# Poly_Piezo.net
KiCad netlist of a schematic drawn in EAGLE
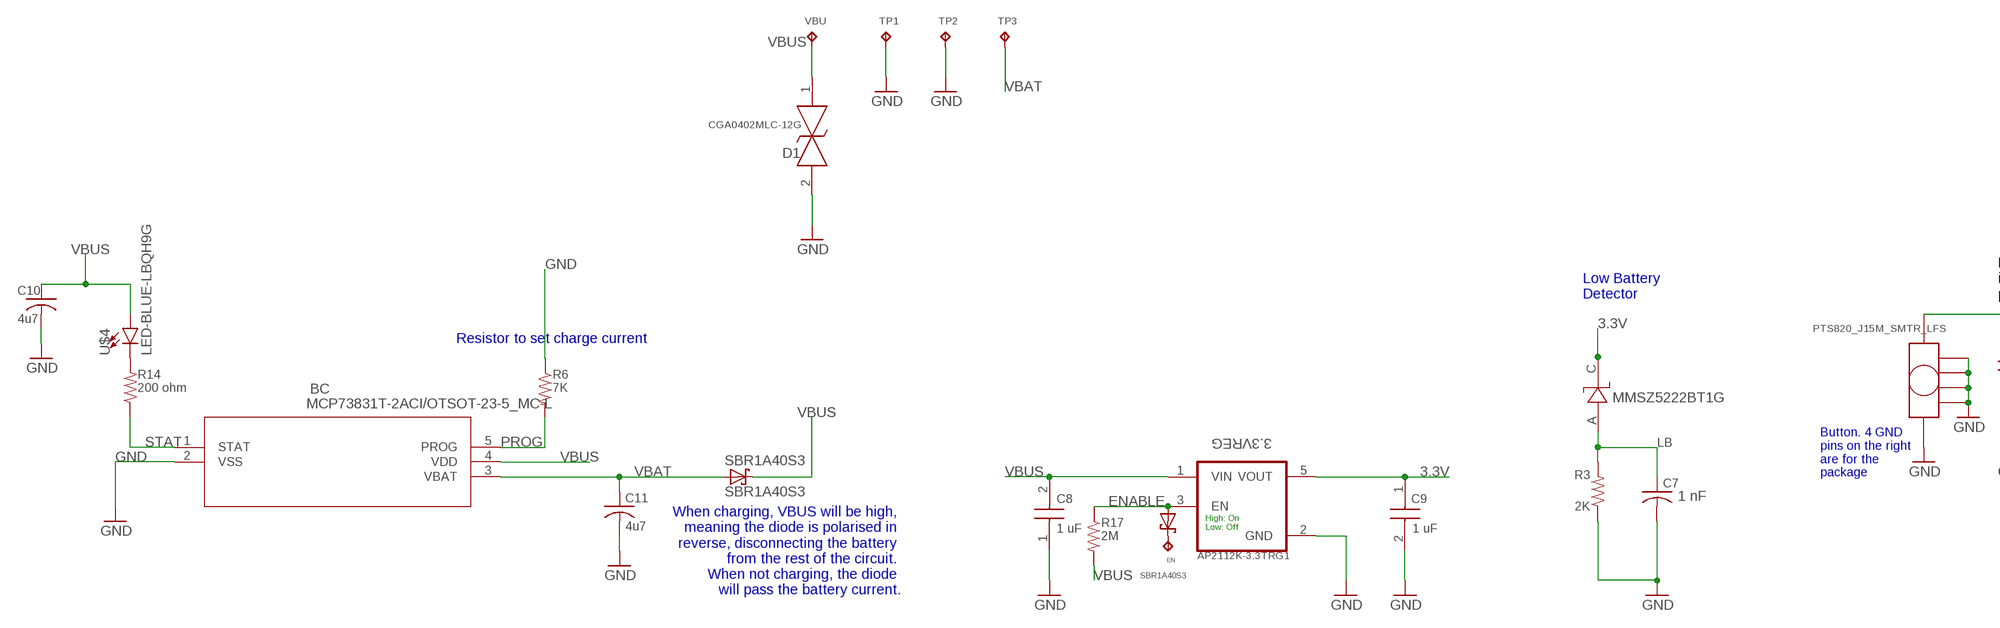
[diagram p0: schematic, sheet 1, part 1 of 2]
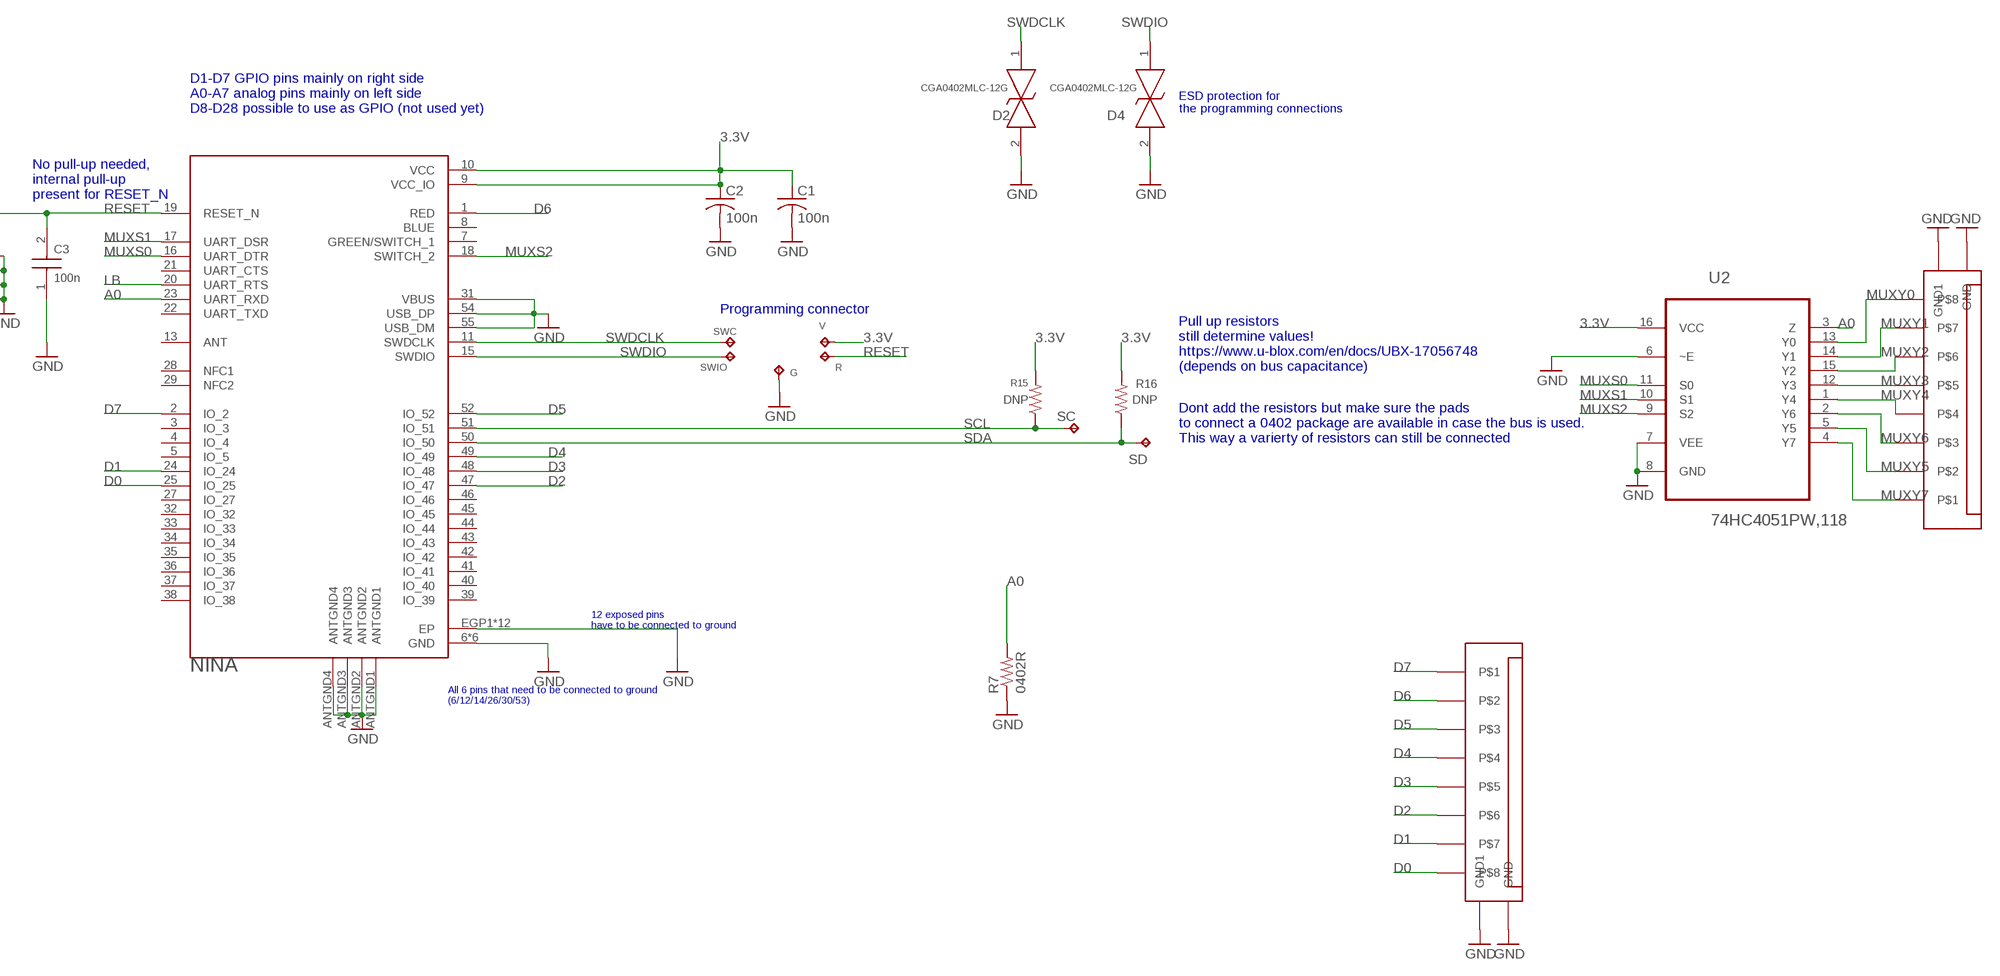
[diagram p1: schematic, sheet 1, part 2 of 2]

(export (version "E")
  (design (tool "Eeschema 10.0.6"))
  (components
    (comp (ref "3.3VREG")
      (value "AP2112K-3.3TRG1")
      (footprint "eagle-import:SOT95P285X140-5N")
      (fields (field (name "MF") "Diodes Inc."))
      (libsource (lib "eagle-import") (part "AP2112K-3.3TRG1"))
    )
    (comp (ref "BC")
      (value "MCP73831T-2ACI/OTSOT-23-5_MC-L")
      (footprint "eagle-import:SOT-23-5_MC-L")
      (fields (field (name "MANUFACTURER_PART_NUMBER") "MCP73831T-2ACI/OT"))
      (libsource (lib "eagle-import") (part "MCP73831T-2ACI/OTSOT-23-5_MC-L"))
    )
    (comp (ref "BUTTON")
      (value "PTS820_J15M_SMTR_LFS")
      (footprint "eagle-import:PTS820_J15")
      (fields
        (field (name "MANUFACTURER_PART_NUMBER") "PTS820 J15M SMTR LFS")
        (field (name "MOUSER_PART_NUMBER") "611-PTS820J15MSMTR")
        (field (name "RS_PART_NUMBER") "1359503P")
      )
      (libsource (lib "eagle-import") (part "PTS820_J15M_SMTR_LFS"))
    )
    (comp (ref "C1")
      (value "100n")
      (footprint "eagle-import:C0402")
      (libsource (lib "eagle-import") (part "C-USC0402"))
    )
    (comp (ref "C2")
      (value "100n")
      (footprint "eagle-import:C0402")
      (libsource (lib "eagle-import") (part "C-USC0402"))
    )
    (comp (ref "C3")
      (value "100n")
      (footprint "eagle-import:CAPC1005X33N")
      (fields
        (field (name "MANUFACTURER_PART_NUMBER") "JMK105BJ105KP-F")
        (field (name "MOUSER_PART_NUMBER") "963-JMK105BJ105KP-F")
      )
      (libsource (lib "eagle-import") (part "JMK105BJ105KP-F"))
    )
    (comp (ref "C7")
      (value "1 nF")
      (footprint "eagle-import:C0402")
      (libsource (lib "eagle-import") (part "C-USC0402"))
    )
    (comp (ref "C8")
      (value "1 uF")
      (footprint "eagle-import:CAPC1005X33N")
      (fields
        (field (name "MANUFACTURER_PART_NUMBER") "JMK105BJ105KP-F")
        (field (name "MOUSER_PART_NUMBER") "963-JMK105BJ105KP-F")
      )
      (libsource (lib "eagle-import") (part "JMK105BJ105KP-F"))
    )
    (comp (ref "C9")
      (value "1 uF")
      (footprint "eagle-import:CAPC1005X33N")
      (fields
        (field (name "MANUFACTURER_PART_NUMBER") "JMK105BJ105KP-F")
        (field (name "MOUSER_PART_NUMBER") "963-JMK105BJ105KP-F")
      )
      (libsource (lib "eagle-import") (part "JMK105BJ105KP-F"))
    )
    (comp (ref "C10")
      (value "4u7")
      (footprint "eagle-import:C0402")
      (libsource (lib "eagle-import") (part "C-USC0402"))
    )
    (comp (ref "C11")
      (value "4u7")
      (footprint "eagle-import:C0402")
      (libsource (lib "eagle-import") (part "C-USC0402"))
    )
    (comp (ref "D1")
      (value "CGA0402MLC-12G")
      (footprint "eagle-import:CGA0402MLC12G")
      (fields (field (name "MOUSER_PART_NUMBER") "652-CGA0402MLC-12G"))
      (libsource (lib "eagle-import") (part "CGA0402MLC-12G"))
    )
    (comp (ref "D2")
      (value "CGA0402MLC-12G")
      (footprint "eagle-import:CGA0402MLC12G")
      (fields (field (name "MOUSER_PART_NUMBER") "652-CGA0402MLC-12G"))
      (libsource (lib "eagle-import") (part "CGA0402MLC-12G"))
    )
    (comp (ref "D4")
      (value "CGA0402MLC-12G")
      (footprint "eagle-import:CGA0402MLC12G")
      (fields (field (name "MOUSER_PART_NUMBER") "652-CGA0402MLC-12G"))
      (libsource (lib "eagle-import") (part "CGA0402MLC-12G"))
    )
    (comp (ref "EN")
      (value "CUSTOM_HOLE1")
      (footprint "eagle-import:CUSTOM_HOLE")
      (libsource (lib "eagle-import") (part "CUSTOM_HOLE1"))
    )
    (comp (ref "G")
      (value "TPB1,27")
      (footprint "eagle-import:B1,27")
      (libsource (lib "eagle-import") (part "TPB1,27"))
    )
    (comp (ref "MMSZ5222BT1G")
      (value "MMSZ5222BT1G")
      (footprint "eagle-import:SOD−123")
      (libsource (lib "eagle-import") (part "MMSZ5222BT1G"))
    )
    (comp (ref "R")
      (value "TPB1,27")
      (footprint "eagle-import:B1,27")
      (libsource (lib "eagle-import") (part "TPB1,27"))
    )
    (comp (ref "R3")
      (value "2K")
      (footprint "eagle-import:RESC1005X40N")
      (libsource (lib "eagle-import") (part "0402R"))
    )
    (comp (ref "R6")
      (value "7K")
      (footprint "eagle-import:RESC1005X40N")
      (libsource (lib "eagle-import") (part "0402R"))
    )
    (comp (ref "R7")
      (value "0402R")
      (footprint "eagle-import:RESC1005X40N")
      (libsource (lib "eagle-import") (part "0402R"))
    )
    (comp (ref "R14")
      (value "200 ohm")
      (footprint "eagle-import:RESC1005X40N")
      (libsource (lib "eagle-import") (part "0402R"))
    )
    (comp (ref "R15")
      (value "DNP")
      (footprint "eagle-import:RESC1005X40N")
      (libsource (lib "eagle-import") (part "0402R"))
    )
    (comp (ref "R16")
      (value "DNP")
      (footprint "eagle-import:RESC1005X40N")
      (libsource (lib "eagle-import") (part "0402R"))
    )
    (comp (ref "R17")
      (value "2M")
      (footprint "eagle-import:RESC1005X40N")
      (libsource (lib "eagle-import") (part "0402R"))
    )
    (comp (ref "SBR1A40S3")
      (value "SBR1A40S3")
      (footprint "eagle-import:SOD323")
      (libsource (lib "eagle-import") (part "SBR1A40S3"))
    )
    (comp (ref "SC")
      (value "CUSTOM_HOLE1")
      (footprint "eagle-import:CUSTOM_HOLE")
      (libsource (lib "eagle-import") (part "CUSTOM_HOLE1"))
    )
    (comp (ref "SD")
      (value "CUSTOM_HOLE1")
      (footprint "eagle-import:CUSTOM_HOLE")
      (libsource (lib "eagle-import") (part "CUSTOM_HOLE1"))
    )
    (comp (ref "SWC")
      (value "TPB1,27")
      (footprint "eagle-import:B1,27")
      (libsource (lib "eagle-import") (part "TPB1,27"))
    )
    (comp (ref "SWIO")
      (value "TPB1,27")
      (footprint "eagle-import:B1,27")
      (libsource (lib "eagle-import") (part "TPB1,27"))
    )
    (comp (ref "TP1")
      (value "CUSTOM_HOLE1")
      (footprint "eagle-import:CUSTOM_HOLE")
      (libsource (lib "eagle-import") (part "CUSTOM_HOLE1"))
    )
    (comp (ref "TP2")
      (value "CUSTOM_HOLE1")
      (footprint "eagle-import:CUSTOM_HOLE")
      (libsource (lib "eagle-import") (part "CUSTOM_HOLE1"))
    )
    (comp (ref "TP3")
      (value "CUSTOM_HOLE1")
      (footprint "eagle-import:CUSTOM_HOLE")
      (libsource (lib "eagle-import") (part "CUSTOM_HOLE1"))
    )
    (comp (ref "U$1")
      (value "XF3M(1)-0815-1B")
      (footprint "eagle-import:XF3M(1)-0815-1B")
      (libsource (lib "eagle-import") (part "XF3M(1)-0815-1B"))
    )
    (comp (ref "U$2")
      (value "SBR1A40S3")
      (footprint "eagle-import:SOD323")
      (libsource (lib "eagle-import") (part "SBR1A40S3"))
    )
    (comp (ref "U$3")
      (value "XF3M(1)-0815-1B")
      (footprint "eagle-import:XF3M(1)-0815-1B")
      (libsource (lib "eagle-import") (part "XF3M(1)-0815-1B"))
    )
    (comp (ref "U$4")
      (value "LED-BLUE-LBQH9G")
      (footprint "eagle-import:LBQH9G-0402")
      (libsource (lib "eagle-import") (part "LED-BLUE-LBQH9G"))
    )
    (comp (ref "U1")
      (value "NINA")
      (footprint "eagle-import:XCVR_NINA-B306")
      (fields (field (name "MF") "U-Blox America Inc.") (field (name "MP") "NINA-B311-00B"))
      (libsource (lib "eagle-import") (part "NINA-B306"))
    )
    (comp (ref "U2")
      (value "74HC4051PW,118")
      (footprint "eagle-import:SOP65P640X110-16N")
      (fields (field (name "MF") "Nexperia USA Inc."))
      (libsource (lib "eagle-import") (part "74HC4051PW,118"))
    )
    (comp (ref "V")
      (value "TPB1,27")
      (footprint "eagle-import:B1,27")
      (libsource (lib "eagle-import") (part "TPB1,27"))
    )
    (comp (ref "VBU")
      (value "CUSTOM_HOLE1")
      (footprint "eagle-import:CUSTOM_HOLE")
      (libsource (lib "eagle-import") (part "CUSTOM_HOLE1"))
    )
  )
  (nets
    (net (code "1") (name "/3.3V") (class "Default")
      (node (ref "3.3VREG") (pin "5") (pinfunction "VOUT_5") (pintype "power_in"))
      (node (ref "C1") (pin "1") (pinfunction "1_1") (pintype "passive"))
      (node (ref "C2") (pin "1") (pinfunction "1_1") (pintype "passive"))
      (node (ref "C9") (pin "1") (pinfunction "1_1") (pintype "bidirectional"))
      (node (ref "MMSZ5222BT1G") (pin "C") (pinfunction "C_C") (pintype "bidirectional"))
      (node (ref "R15") (pin "2") (pinfunction "2_2") (pintype "passive"))
      (node (ref "R16") (pin "2") (pinfunction "2_2") (pintype "passive"))
      (node (ref "U1") (pin "10") (pinfunction "VCC_10") (pintype "power_in"))
      (node (ref "U1") (pin "9") (pinfunction "VCC_IO_9") (pintype "power_in"))
      (node (ref "U2") (pin "16") (pinfunction "VCC_16") (pintype "power_in"))
      (node (ref "V") (pin "TP") (pinfunction "TP_TP") (pintype "input"))
    )
    (net (code "2") (name "/A0") (class "Default")
      (node (ref "R7") (pin "2") (pinfunction "2_2") (pintype "passive"))
      (node (ref "U1") (pin "23") (pinfunction "UART_RXD_23") (pintype "input"))
      (node (ref "U2") (pin "3") (pinfunction "Z_3") (pintype "bidirectional"))
    )
    (net (code "3") (name "/D0") (class "Default")
      (node (ref "U$1") (pin "P$8") (pinfunction "P$8_P$8") (pintype "bidirectional"))
      (node (ref "U1") (pin "25") (pinfunction "IO_25_25") (pintype "bidirectional"))
    )
    (net (code "4") (name "/D1") (class "Default")
      (node (ref "U$1") (pin "P$7") (pinfunction "P$7_P$7") (pintype "bidirectional"))
      (node (ref "U1") (pin "24") (pinfunction "IO_24_24") (pintype "bidirectional"))
    )
    (net (code "5") (name "/D2") (class "Default")
      (node (ref "U$1") (pin "P$6") (pinfunction "P$6_P$6") (pintype "bidirectional"))
      (node (ref "U1") (pin "47") (pinfunction "IO_47_47") (pintype "bidirectional"))
    )
    (net (code "6") (name "/D3") (class "Default")
      (node (ref "U$1") (pin "P$5") (pinfunction "P$5_P$5") (pintype "bidirectional"))
      (node (ref "U1") (pin "48") (pinfunction "IO_48_48") (pintype "bidirectional"))
    )
    (net (code "7") (name "/D4") (class "Default")
      (node (ref "U$1") (pin "P$4") (pinfunction "P$4_P$4") (pintype "bidirectional"))
      (node (ref "U1") (pin "49") (pinfunction "IO_49_49") (pintype "bidirectional"))
    )
    (net (code "8") (name "/D5") (class "Default")
      (node (ref "U$1") (pin "P$3") (pinfunction "P$3_P$3") (pintype "bidirectional"))
      (node (ref "U1") (pin "52") (pinfunction "IO_52_52") (pintype "bidirectional"))
    )
    (net (code "9") (name "/D6") (class "Default")
      (node (ref "U$1") (pin "P$2") (pinfunction "P$2_P$2") (pintype "bidirectional"))
      (node (ref "U1") (pin "1") (pinfunction "RED_1") (pintype "output"))
    )
    (net (code "10") (name "/D7") (class "Default")
      (node (ref "U$1") (pin "P$1") (pinfunction "P$1_P$1") (pintype "bidirectional"))
      (node (ref "U1") (pin "2") (pinfunction "IO_2_2") (pintype "bidirectional"))
    )
    (net (code "11") (name "/ENABLE") (class "Default")
      (node (ref "3.3VREG") (pin "3") (pinfunction "EN_3") (pintype "input"))
      (node (ref "R17") (pin "1") (pinfunction "1_1") (pintype "passive"))
      (node (ref "U$2") (pin "A") (pinfunction "A_A") (pintype "passive"))
    )
    (net (code "12") (name "/LB") (class "Default")
      (node (ref "C7") (pin "1") (pinfunction "1_1") (pintype "passive"))
      (node (ref "MMSZ5222BT1G") (pin "A") (pinfunction "A_A") (pintype "bidirectional"))
      (node (ref "R3") (pin "2") (pinfunction "2_2") (pintype "passive"))
      (node (ref "U1") (pin "20") (pinfunction "UART_RTS_20") (pintype "output"))
    )
    (net (code "13") (name "/MUXS0") (class "Default")
      (node (ref "U1") (pin "16") (pinfunction "UART_DTR_16") (pintype "output"))
      (node (ref "U2") (pin "11") (pinfunction "S0_11") (pintype "input"))
    )
    (net (code "14") (name "/MUXS1") (class "Default")
      (node (ref "U1") (pin "17") (pinfunction "UART_DSR_17") (pintype "input"))
      (node (ref "U2") (pin "10") (pinfunction "S1_10") (pintype "input"))
    )
    (net (code "15") (name "/MUXS2") (class "Default")
      (node (ref "U1") (pin "18") (pinfunction "SWITCH_2_18") (pintype "input"))
      (node (ref "U2") (pin "9") (pinfunction "S2_9") (pintype "input"))
    )
    (net (code "16") (name "/MUXY0") (class "Default")
      (node (ref "U$3") (pin "P$8") (pinfunction "P$8_P$8") (pintype "bidirectional"))
      (node (ref "U2") (pin "13") (pinfunction "Y0_13") (pintype "bidirectional"))
    )
    (net (code "17") (name "/MUXY1") (class "Default")
      (node (ref "U$3") (pin "P$7") (pinfunction "P$7_P$7") (pintype "bidirectional"))
      (node (ref "U2") (pin "14") (pinfunction "Y1_14") (pintype "bidirectional"))
    )
    (net (code "18") (name "/MUXY2") (class "Default")
      (node (ref "U$3") (pin "P$6") (pinfunction "P$6_P$6") (pintype "bidirectional"))
      (node (ref "U2") (pin "15") (pinfunction "Y2_15") (pintype "bidirectional"))
    )
    (net (code "19") (name "/MUXY3") (class "Default")
      (node (ref "U$3") (pin "P$5") (pinfunction "P$5_P$5") (pintype "bidirectional"))
      (node (ref "U2") (pin "12") (pinfunction "Y3_12") (pintype "bidirectional"))
    )
    (net (code "20") (name "/MUXY4") (class "Default")
      (node (ref "U$3") (pin "P$4") (pinfunction "P$4_P$4") (pintype "bidirectional"))
      (node (ref "U2") (pin "1") (pinfunction "Y4_1") (pintype "bidirectional"))
    )
    (net (code "21") (name "/MUXY5") (class "Default")
      (node (ref "U$3") (pin "P$2") (pinfunction "P$2_P$2") (pintype "bidirectional"))
      (node (ref "U2") (pin "5") (pinfunction "Y5_5") (pintype "bidirectional"))
    )
    (net (code "22") (name "/MUXY6") (class "Default")
      (node (ref "U$3") (pin "P$3") (pinfunction "P$3_P$3") (pintype "bidirectional"))
      (node (ref "U2") (pin "2") (pinfunction "Y6_2") (pintype "bidirectional"))
    )
    (net (code "23") (name "/MUXY7") (class "Default")
      (node (ref "U$3") (pin "P$1") (pinfunction "P$1_P$1") (pintype "bidirectional"))
      (node (ref "U2") (pin "4") (pinfunction "Y7_4") (pintype "bidirectional"))
    )
    (net (code "24") (name "/PROG") (class "Default")
      (node (ref "BC") (pin "5") (pinfunction "PROG_5") (pintype "passive"))
      (node (ref "R6") (pin "2") (pinfunction "2_2") (pintype "passive"))
    )
    (net (code "25") (name "/RESET") (class "Default")
      (node (ref "BUTTON") (pin "2") (pinfunction "2_2") (pintype "bidirectional"))
      (node (ref "C3") (pin "2") (pinfunction "2_2") (pintype "bidirectional"))
      (node (ref "R") (pin "TP") (pinfunction "TP_TP") (pintype "input"))
      (node (ref "U1") (pin "19") (pinfunction "RESET_N_19") (pintype "input"))
    )
    (net (code "26") (name "/SCL") (class "Default")
      (node (ref "R15") (pin "1") (pinfunction "1_1") (pintype "passive"))
      (node (ref "SC") (pin "P$1") (pinfunction "TP_P$1") (pintype "input"))
      (node (ref "U1") (pin "51") (pinfunction "IO_51_51") (pintype "bidirectional"))
    )
    (net (code "27") (name "/SDA") (class "Default")
      (node (ref "R16") (pin "1") (pinfunction "1_1") (pintype "passive"))
      (node (ref "SD") (pin "P$1") (pinfunction "TP_P$1") (pintype "input"))
      (node (ref "U1") (pin "50") (pinfunction "IO_50_50") (pintype "bidirectional"))
    )
    (net (code "28") (name "/STAT") (class "Default")
      (node (ref "BC") (pin "1") (pinfunction "STAT_1") (pintype "passive"))
      (node (ref "R14") (pin "1") (pinfunction "1_1") (pintype "passive"))
    )
    (net (code "29") (name "/SWDCLK") (class "Default")
      (node (ref "D2") (pin "1") (pinfunction "1_1") (pintype "bidirectional"))
      (node (ref "SWC") (pin "TP") (pinfunction "TP_TP") (pintype "input"))
      (node (ref "U1") (pin "11") (pinfunction "SWDCLK_11") (pintype "bidirectional"))
    )
    (net (code "30") (name "/SWDIO") (class "Default")
      (node (ref "D4") (pin "1") (pinfunction "1_1") (pintype "bidirectional"))
      (node (ref "SWIO") (pin "TP") (pinfunction "TP_TP") (pintype "input"))
      (node (ref "U1") (pin "15") (pinfunction "SWDIO_15") (pintype "bidirectional"))
    )
    (net (code "31") (name "/VBAT") (class "Default")
      (node (ref "BC") (pin "3") (pinfunction "VBAT_3") (pintype "passive"))
      (node (ref "C11") (pin "1") (pinfunction "1_1") (pintype "passive"))
      (node (ref "SBR1A40S3") (pin "A") (pinfunction "A_A") (pintype "passive"))
      (node (ref "TP3") (pin "P$1") (pinfunction "TP_P$1") (pintype "input"))
    )
    (net (code "32") (name "/VBUS") (class "Default")
      (node (ref "3.3VREG") (pin "1") (pinfunction "VIN_1") (pintype "power_in"))
      (node (ref "BC") (pin "4") (pinfunction "VDD_4") (pintype "passive"))
      (node (ref "C10") (pin "1") (pinfunction "1_1") (pintype "passive"))
      (node (ref "C8") (pin "2") (pinfunction "2_2") (pintype "bidirectional"))
      (node (ref "D1") (pin "1") (pinfunction "1_1") (pintype "bidirectional"))
      (node (ref "R17") (pin "2") (pinfunction "2_2") (pintype "passive"))
      (node (ref "SBR1A40S3") (pin "C") (pinfunction "C_C") (pintype "passive"))
      (node (ref "U$4") (pin "A") (pinfunction "A_A") (pintype "passive"))
      (node (ref "VBU") (pin "P$1") (pinfunction "TP_P$1") (pintype "input"))
    )
    (net (code "33") (name "GND") (class "Default")
      (node (ref "3.3VREG") (pin "2") (pinfunction "GND_2") (pintype "power_in"))
      (node (ref "BC") (pin "2") (pinfunction "VSS_2") (pintype "passive"))
      (node (ref "BUTTON") (pin "1") (pinfunction "1_1") (pintype "bidirectional"))
      (node (ref "BUTTON") (pin "P$1") (pinfunction "P$1_P$1") (pintype "bidirectional"))
      (node (ref "BUTTON") (pin "P$2") (pinfunction "P$2_P$2") (pintype "bidirectional"))
      (node (ref "BUTTON") (pin "P$3") (pinfunction "P$3_P$3") (pintype "bidirectional"))
      (node (ref "BUTTON") (pin "P$4") (pinfunction "P$4_P$4") (pintype "bidirectional"))
      (node (ref "C1") (pin "2") (pinfunction "2_2") (pintype "passive"))
      (node (ref "C10") (pin "2") (pinfunction "2_2") (pintype "passive"))
      (node (ref "C11") (pin "2") (pinfunction "2_2") (pintype "passive"))
      (node (ref "C2") (pin "2") (pinfunction "2_2") (pintype "passive"))
      (node (ref "C3") (pin "1") (pinfunction "1_1") (pintype "bidirectional"))
      (node (ref "C7") (pin "2") (pinfunction "2_2") (pintype "passive"))
      (node (ref "C8") (pin "1") (pinfunction "1_1") (pintype "bidirectional"))
      (node (ref "C9") (pin "2") (pinfunction "2_2") (pintype "bidirectional"))
      (node (ref "D1") (pin "2") (pinfunction "2_2") (pintype "bidirectional"))
      (node (ref "D2") (pin "2") (pinfunction "2_2") (pintype "bidirectional"))
      (node (ref "D4") (pin "2") (pinfunction "2_2") (pintype "bidirectional"))
      (node (ref "G") (pin "TP") (pinfunction "TP_TP") (pintype "input"))
      (node (ref "R3") (pin "1") (pinfunction "1_1") (pintype "passive"))
      (node (ref "R6") (pin "1") (pinfunction "1_1") (pintype "passive"))
      (node (ref "R7") (pin "1") (pinfunction "1_1") (pintype "passive"))
      (node (ref "TP1") (pin "P$1") (pinfunction "TP_P$1") (pintype "input"))
      (node (ref "TP2") (pin "P$1") (pinfunction "TP_P$1") (pintype "input"))
      (node (ref "U$1") (pin "P$10") (pinfunction "GND_P$10") (pintype "bidirectional"))
      (node (ref "U$1") (pin "P$9") (pinfunction "GND1_P$9") (pintype "bidirectional"))
      (node (ref "U$3") (pin "P$10") (pinfunction "GND_P$10") (pintype "bidirectional"))
      (node (ref "U$3") (pin "P$9") (pinfunction "GND1_P$9") (pintype "bidirectional"))
      (node (ref "U1") (pin "12") (pinfunction "GND_12") (pintype "power_in"))
      (node (ref "U1") (pin "14") (pinfunction "GND_14") (pintype "power_in"))
      (node (ref "U1") (pin "26") (pinfunction "GND_26") (pintype "power_in"))
      (node (ref "U1") (pin "30") (pinfunction "GND_30") (pintype "power_in"))
      (node (ref "U1") (pin "31") (pinfunction "VBUS_31") (pintype "bidirectional"))
      (node (ref "U1") (pin "53") (pinfunction "GND_53") (pintype "power_in"))
      (node (ref "U1") (pin "54") (pinfunction "USB_DP_54") (pintype "bidirectional"))
      (node (ref "U1") (pin "55") (pinfunction "USB_DM_55") (pintype "bidirectional"))
      (node (ref "U1") (pin "6") (pinfunction "GND_6") (pintype "power_in"))
      (node (ref "U1") (pin "ANTGND1") (pinfunction "ANTGND1_ANTGND1") (pintype "bidirectional"))
      (node (ref "U1") (pin "ANTGND2") (pinfunction "ANTGND2_ANTGND2") (pintype "bidirectional"))
      (node (ref "U1") (pin "ANTGND3") (pinfunction "ANTGND3_ANTGND3") (pintype "bidirectional"))
      (node (ref "U1") (pin "ANTGND4") (pinfunction "ANTGND4_ANTGND4") (pintype "bidirectional"))
      (node (ref "U1") (pin "EGP1") (pinfunction "EP_EGP1") (pintype "power_in"))
      (node (ref "U1") (pin "EGP10") (pinfunction "EP_EGP10") (pintype "power_in"))
      (node (ref "U1") (pin "EGP11") (pinfunction "EP_EGP11") (pintype "power_in"))
      (node (ref "U1") (pin "EGP12") (pinfunction "EP_EGP12") (pintype "power_in"))
      (node (ref "U1") (pin "EGP2") (pinfunction "EP_EGP2") (pintype "power_in"))
      (node (ref "U1") (pin "EGP3") (pinfunction "EP_EGP3") (pintype "power_in"))
      (node (ref "U1") (pin "EGP4") (pinfunction "EP_EGP4") (pintype "power_in"))
      (node (ref "U1") (pin "EGP5") (pinfunction "EP_EGP5") (pintype "power_in"))
      (node (ref "U1") (pin "EGP6") (pinfunction "EP_EGP6") (pintype "power_in"))
      (node (ref "U1") (pin "EGP7") (pinfunction "EP_EGP7") (pintype "power_in"))
      (node (ref "U1") (pin "EGP8") (pinfunction "EP_EGP8") (pintype "power_in"))
      (node (ref "U1") (pin "EGP9") (pinfunction "EP_EGP9") (pintype "power_in"))
      (node (ref "U2") (pin "6") (pinfunction "~{E}_6") (pintype "input"))
      (node (ref "U2") (pin "7") (pinfunction "VEE_7") (pintype "power_in"))
      (node (ref "U2") (pin "8") (pinfunction "GND_8") (pintype "passive"))
    )
    (net (code "34") (name "Net-(EN-TP)") (class "Default")
      (node (ref "EN") (pin "P$1") (pinfunction "TP_P$1") (pintype "input"))
      (node (ref "U$2") (pin "C") (pinfunction "C_C") (pintype "passive"))
    )
    (net (code "35") (name "Net-(R14-Pad2)") (class "Default")
      (node (ref "R14") (pin "2") (pinfunction "2_2") (pintype "passive"))
      (node (ref "U$4") (pin "C") (pinfunction "C_C") (pintype "passive"))
    )
    (net (code "36") (name "unconnected-(U1-ANT-Pad13)") (class "Default")
      (node (ref "U1") (pin "13") (pinfunction "ANT_13") (pintype "bidirectional"))
    )
    (net (code "37") (name "unconnected-(U1-BLUE-Pad8)") (class "Default")
      (node (ref "U1") (pin "8") (pinfunction "BLUE_8") (pintype "output"))
    )
    (net (code "38") (name "unconnected-(U1-GREEN{slash}SWITCH_1-Pad7)") (class "Default")
      (node (ref "U1") (pin "7") (pinfunction "GREEN/SWITCH_1_7") (pintype "bidirectional"))
    )
    (net (code "39") (name "unconnected-(U1-IO_3-Pad3)") (class "Default")
      (node (ref "U1") (pin "3") (pinfunction "IO_3_3") (pintype "bidirectional"))
    )
    (net (code "40") (name "unconnected-(U1-IO_4-Pad4)") (class "Default")
      (node (ref "U1") (pin "4") (pinfunction "IO_4_4") (pintype "bidirectional"))
    )
    (net (code "41") (name "unconnected-(U1-IO_5-Pad5)") (class "Default")
      (node (ref "U1") (pin "5") (pinfunction "IO_5_5") (pintype "bidirectional"))
    )
    (net (code "42") (name "unconnected-(U1-IO_27-Pad27)") (class "Default")
      (node (ref "U1") (pin "27") (pinfunction "IO_27_27") (pintype "bidirectional"))
    )
    (net (code "43") (name "unconnected-(U1-IO_32-Pad32)") (class "Default")
      (node (ref "U1") (pin "32") (pinfunction "IO_32_32") (pintype "bidirectional"))
    )
    (net (code "44") (name "unconnected-(U1-IO_33-Pad33)") (class "Default")
      (node (ref "U1") (pin "33") (pinfunction "IO_33_33") (pintype "bidirectional"))
    )
    (net (code "45") (name "unconnected-(U1-IO_34-Pad34)") (class "Default")
      (node (ref "U1") (pin "34") (pinfunction "IO_34_34") (pintype "bidirectional"))
    )
    (net (code "46") (name "unconnected-(U1-IO_35-Pad35)") (class "Default")
      (node (ref "U1") (pin "35") (pinfunction "IO_35_35") (pintype "bidirectional"))
    )
    (net (code "47") (name "unconnected-(U1-IO_36-Pad36)") (class "Default")
      (node (ref "U1") (pin "36") (pinfunction "IO_36_36") (pintype "bidirectional"))
    )
    (net (code "48") (name "unconnected-(U1-IO_37-Pad37)") (class "Default")
      (node (ref "U1") (pin "37") (pinfunction "IO_37_37") (pintype "bidirectional"))
    )
    (net (code "49") (name "unconnected-(U1-IO_38-Pad38)") (class "Default")
      (node (ref "U1") (pin "38") (pinfunction "IO_38_38") (pintype "bidirectional"))
    )
    (net (code "50") (name "unconnected-(U1-IO_39-Pad39)") (class "Default")
      (node (ref "U1") (pin "39") (pinfunction "IO_39_39") (pintype "bidirectional"))
    )
    (net (code "51") (name "unconnected-(U1-IO_40-Pad40)") (class "Default")
      (node (ref "U1") (pin "40") (pinfunction "IO_40_40") (pintype "bidirectional"))
    )
    (net (code "52") (name "unconnected-(U1-IO_41-Pad41)") (class "Default")
      (node (ref "U1") (pin "41") (pinfunction "IO_41_41") (pintype "bidirectional"))
    )
    (net (code "53") (name "unconnected-(U1-IO_42-Pad42)") (class "Default")
      (node (ref "U1") (pin "42") (pinfunction "IO_42_42") (pintype "bidirectional"))
    )
    (net (code "54") (name "unconnected-(U1-IO_43-Pad43)") (class "Default")
      (node (ref "U1") (pin "43") (pinfunction "IO_43_43") (pintype "bidirectional"))
    )
    (net (code "55") (name "unconnected-(U1-IO_44-Pad44)") (class "Default")
      (node (ref "U1") (pin "44") (pinfunction "IO_44_44") (pintype "bidirectional"))
    )
    (net (code "56") (name "unconnected-(U1-IO_45-Pad45)") (class "Default")
      (node (ref "U1") (pin "45") (pinfunction "IO_45_45") (pintype "bidirectional"))
    )
    (net (code "57") (name "unconnected-(U1-IO_46-Pad46)") (class "Default")
      (node (ref "U1") (pin "46") (pinfunction "IO_46_46") (pintype "bidirectional"))
    )
    (net (code "58") (name "unconnected-(U1-NFC1-Pad28)") (class "Default")
      (node (ref "U1") (pin "28") (pinfunction "NFC1_28") (pintype "bidirectional"))
    )
    (net (code "59") (name "unconnected-(U1-NFC2-Pad29)") (class "Default")
      (node (ref "U1") (pin "29") (pinfunction "NFC2_29") (pintype "bidirectional"))
    )
    (net (code "60") (name "unconnected-(U1-UART_CTS-Pad21)") (class "Default")
      (node (ref "U1") (pin "21") (pinfunction "UART_CTS_21") (pintype "input"))
    )
    (net (code "61") (name "unconnected-(U1-UART_TXD-Pad22)") (class "Default")
      (node (ref "U1") (pin "22") (pinfunction "UART_TXD_22") (pintype "output"))
    )
  )
)
